# DAC_board.net
KiCad netlist of a schematic drawn in Altium Designer
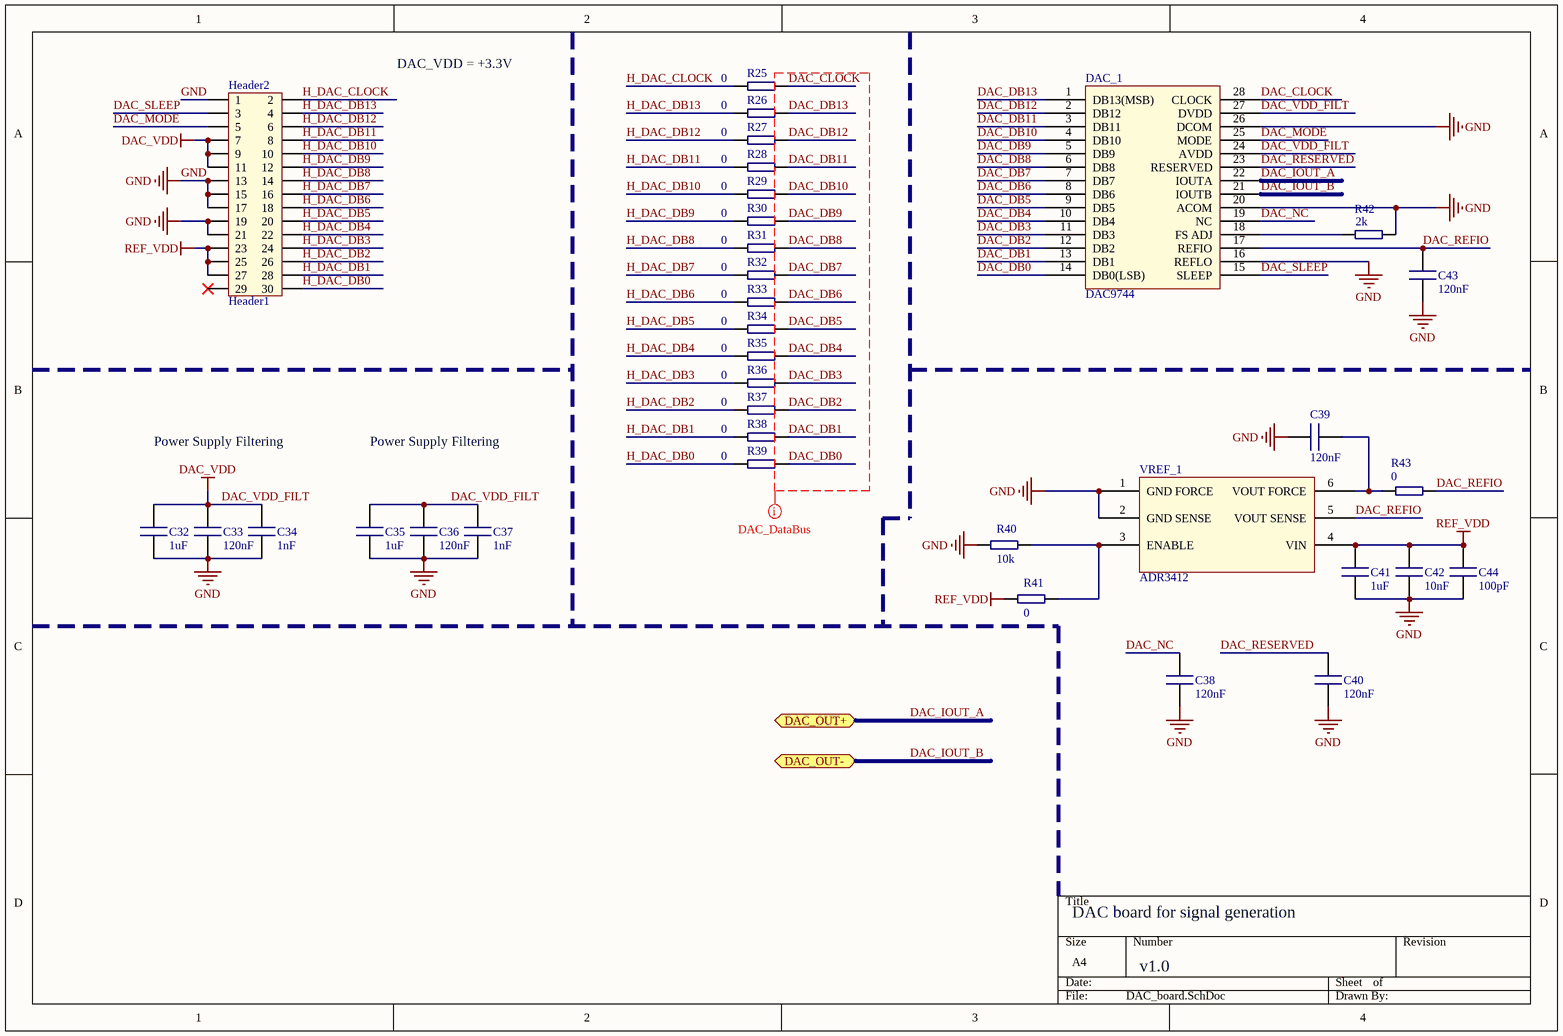
[diagram p0: DAC_board.SchDoc]

(export (version "E")
  (design (tool "Eeschema 10.0.6"))
  (components
    (comp (ref "C32")
      (value "1uF")
      (footprint "0805 SMD Passive")
      (description "SMD Capacitor")
      (fields (field (name "Comment") "Cap1"))
      (libsource (lib "RadioProjectSchLib") (part "Cap1"))
    )
    (comp (ref "C33")
      (value "120nF")
      (footprint "0805 SMD Passive")
      (description "SMD Capacitor")
      (fields (field (name "Comment") "Cap1"))
      (libsource (lib "RadioProjectSchLib") (part "Cap1"))
    )
    (comp (ref "C34")
      (value "1nF")
      (footprint "0805 SMD Passive")
      (description "SMD Capacitor")
      (fields (field (name "Comment") "Cap1"))
      (libsource (lib "RadioProjectSchLib") (part "Cap1"))
    )
    (comp (ref "C35")
      (value "1uF")
      (footprint "0805 SMD Passive")
      (description "SMD Capacitor")
      (fields (field (name "Comment") "Cap1"))
      (libsource (lib "RadioProjectSchLib") (part "Cap1"))
    )
    (comp (ref "C36")
      (value "120nF")
      (footprint "0805 SMD Passive")
      (description "SMD Capacitor")
      (fields (field (name "Comment") "Cap1"))
      (libsource (lib "RadioProjectSchLib") (part "Cap1"))
    )
    (comp (ref "C37")
      (value "1nF")
      (footprint "0805 SMD Passive")
      (description "SMD Capacitor")
      (fields (field (name "Comment") "Cap1"))
      (libsource (lib "RadioProjectSchLib") (part "Cap1"))
    )
    (comp (ref "C38")
      (value "120nF")
      (footprint "0805 SMD Passive")
      (description "SMD Capacitor")
      (fields (field (name "Comment") "Cap1"))
      (libsource (lib "RadioProjectSchLib") (part "Cap1"))
    )
    (comp (ref "C39")
      (value "120nF")
      (footprint "0805 SMD Passive")
      (description "SMD Capacitor")
      (fields (field (name "Comment") "Cap1"))
      (libsource (lib "RadioProjectSchLib") (part "Cap1"))
    )
    (comp (ref "C40")
      (value "120nF")
      (footprint "0805 SMD Passive")
      (description "SMD Capacitor")
      (fields (field (name "Comment") "Cap1"))
      (libsource (lib "RadioProjectSchLib") (part "Cap1"))
    )
    (comp (ref "C41")
      (value "1uF")
      (footprint "0805 SMD Passive")
      (description "SMD Capacitor")
      (fields (field (name "Comment") "Cap1"))
      (libsource (lib "RadioProjectSchLib") (part "Cap1"))
    )
    (comp (ref "C42")
      (value "10nF")
      (footprint "0805 SMD Passive")
      (description "SMD Capacitor")
      (fields (field (name "Comment") "Cap1"))
      (libsource (lib "RadioProjectSchLib") (part "Cap1"))
    )
    (comp (ref "C43")
      (value "120nF")
      (footprint "0805 SMD Passive")
      (description "SMD Capacitor")
      (fields (field (name "Comment") "Cap1"))
      (libsource (lib "RadioProjectSchLib") (part "Cap1"))
    )
    (comp (ref "C44")
      (value "100pF")
      (footprint "0805 SMD Passive")
      (description "SMD Capacitor")
      (fields (field (name "Comment") "Cap1"))
      (libsource (lib "RadioProjectSchLib") (part "Cap1"))
    )
    (comp (ref "DAC_1")
      (value "DAC9744")
      (footprint "AD9744")
      (description "Digital Analog Converter")
      (fields (field (name "MANUFACTURER") "Analog Devices") (field (name "PARTNUMBER") "AD9744"))
      (libsource (lib "RadioProjectSchLib") (part "AD9744"))
    )
    (comp (ref "Header2")
      (value "Header1")
      (footprint "Header1")
      (description "29 Pin Header")
      (fields (field (name "PARTNUMBER") "TLW-115-01-G-D-002-RA"))
      (libsource (lib "RadioProjectSchLib") (part "Header1"))
    )
    (comp (ref "R25")
      (value "0")
      (footprint "0805 SMD Passive")
      (description "SMD Resistor")
      (fields (field (name "Comment") "Resistor"))
      (libsource (lib "RadioProjectSchLib") (part "Res1"))
    )
    (comp (ref "R26")
      (value "0")
      (footprint "0805 SMD Passive")
      (description "SMD Resistor")
      (fields (field (name "Comment") "Resistor"))
      (libsource (lib "RadioProjectSchLib") (part "Res1"))
    )
    (comp (ref "R27")
      (value "0")
      (footprint "0805 SMD Passive")
      (description "SMD Resistor")
      (fields (field (name "Comment") "Resistor"))
      (libsource (lib "RadioProjectSchLib") (part "Res1"))
    )
    (comp (ref "R28")
      (value "0")
      (footprint "0805 SMD Passive")
      (description "SMD Resistor")
      (fields (field (name "Comment") "Resistor"))
      (libsource (lib "RadioProjectSchLib") (part "Res1"))
    )
    (comp (ref "R29")
      (value "0")
      (footprint "0805 SMD Passive")
      (description "SMD Resistor")
      (fields (field (name "Comment") "Resistor"))
      (libsource (lib "RadioProjectSchLib") (part "Res1"))
    )
    (comp (ref "R30")
      (value "0")
      (footprint "0805 SMD Passive")
      (description "SMD Resistor")
      (fields (field (name "Comment") "Resistor"))
      (libsource (lib "RadioProjectSchLib") (part "Res1"))
    )
    (comp (ref "R31")
      (value "0")
      (footprint "0805 SMD Passive")
      (description "SMD Resistor")
      (fields (field (name "Comment") "Resistor"))
      (libsource (lib "RadioProjectSchLib") (part "Res1"))
    )
    (comp (ref "R32")
      (value "0")
      (footprint "0805 SMD Passive")
      (description "SMD Resistor")
      (fields (field (name "Comment") "Resistor"))
      (libsource (lib "RadioProjectSchLib") (part "Res1"))
    )
    (comp (ref "R33")
      (value "0")
      (footprint "0805 SMD Passive")
      (description "SMD Resistor")
      (fields (field (name "Comment") "Resistor"))
      (libsource (lib "RadioProjectSchLib") (part "Res1"))
    )
    (comp (ref "R34")
      (value "0")
      (footprint "0805 SMD Passive")
      (description "SMD Resistor")
      (fields (field (name "Comment") "Resistor"))
      (libsource (lib "RadioProjectSchLib") (part "Res1"))
    )
    (comp (ref "R35")
      (value "0")
      (footprint "0805 SMD Passive")
      (description "SMD Resistor")
      (fields (field (name "Comment") "Resistor"))
      (libsource (lib "RadioProjectSchLib") (part "Res1"))
    )
    (comp (ref "R36")
      (value "0")
      (footprint "0805 SMD Passive")
      (description "SMD Resistor")
      (fields (field (name "Comment") "Resistor"))
      (libsource (lib "RadioProjectSchLib") (part "Res1"))
    )
    (comp (ref "R37")
      (value "0")
      (footprint "0805 SMD Passive")
      (description "SMD Resistor")
      (fields (field (name "Comment") "Resistor"))
      (libsource (lib "RadioProjectSchLib") (part "Res1"))
    )
    (comp (ref "R38")
      (value "0")
      (footprint "0805 SMD Passive")
      (description "SMD Resistor")
      (fields (field (name "Comment") "Resistor"))
      (libsource (lib "RadioProjectSchLib") (part "Res1"))
    )
    (comp (ref "R39")
      (value "0")
      (footprint "0805 SMD Passive")
      (description "SMD Resistor")
      (fields (field (name "Comment") "Resistor"))
      (libsource (lib "RadioProjectSchLib") (part "Res1"))
    )
    (comp (ref "R40")
      (value "10k")
      (footprint "0805 SMD Passive")
      (description "SMD Resistor")
      (fields (field (name "Comment") "Resistor"))
      (libsource (lib "RadioProjectSchLib") (part "Res1"))
    )
    (comp (ref "R41")
      (value "0")
      (footprint "0805 SMD Passive")
      (description "SMD Resistor")
      (fields (field (name "Comment") "Resistor"))
      (libsource (lib "RadioProjectSchLib") (part "Res1"))
    )
    (comp (ref "R42")
      (value "2k")
      (footprint "0805 SMD Passive")
      (description "SMD Resistor")
      (fields (field (name "Comment") "Resistor"))
      (libsource (lib "RadioProjectSchLib") (part "Res1"))
    )
    (comp (ref "R43")
      (value "0")
      (footprint "0805 SMD Passive")
      (description "SMD Resistor")
      (fields (field (name "Comment") "Resistor"))
      (libsource (lib "RadioProjectSchLib") (part "Res1"))
    )
    (comp (ref "VREF_1")
      (value "ADR3412")
      (footprint "ADR3412")
      (description "1.2 Voltage Ref Source")
      (fields (field (name "MANUFACTURER") "Analog Devices"))
      (libsource (lib "RadioProjectSchLib") (part "ADR3412"))
    )
  )
  (nets
    (net (code "1") (name "/DAC_CLOCK") (class "Default")
      (node (ref "DAC_1") (pin "28") (pinfunction "CLOCK_28") (pintype "passive"))
      (node (ref "R25") (pin "2") (pinfunction "*_2") (pintype "passive"))
    )
    (net (code "2") (name "/DAC_DB0") (class "Default")
      (node (ref "DAC_1") (pin "14") (pinfunction "DB0(LSB)_14") (pintype "passive"))
      (node (ref "R39") (pin "2") (pinfunction "*_2") (pintype "passive"))
    )
    (net (code "3") (name "/DAC_DB1") (class "Default")
      (node (ref "DAC_1") (pin "13") (pinfunction "DB1_13") (pintype "passive"))
      (node (ref "R38") (pin "2") (pinfunction "*_2") (pintype "passive"))
    )
    (net (code "4") (name "/DAC_DB2") (class "Default")
      (node (ref "DAC_1") (pin "12") (pinfunction "DB2_12") (pintype "passive"))
      (node (ref "R37") (pin "2") (pinfunction "*_2") (pintype "passive"))
    )
    (net (code "5") (name "/DAC_DB3") (class "Default")
      (node (ref "DAC_1") (pin "11") (pinfunction "DB3_11") (pintype "passive"))
      (node (ref "R36") (pin "2") (pinfunction "*_2") (pintype "passive"))
    )
    (net (code "6") (name "/DAC_DB4") (class "Default")
      (node (ref "DAC_1") (pin "10") (pinfunction "DB4_10") (pintype "passive"))
      (node (ref "R35") (pin "2") (pinfunction "*_2") (pintype "passive"))
    )
    (net (code "7") (name "/DAC_DB5") (class "Default")
      (node (ref "DAC_1") (pin "9") (pinfunction "DB5_9") (pintype "passive"))
      (node (ref "R34") (pin "2") (pinfunction "*_2") (pintype "passive"))
    )
    (net (code "8") (name "/DAC_DB6") (class "Default")
      (node (ref "DAC_1") (pin "8") (pinfunction "DB6_8") (pintype "passive"))
      (node (ref "R33") (pin "2") (pinfunction "*_2") (pintype "passive"))
    )
    (net (code "9") (name "/DAC_DB7") (class "Default")
      (node (ref "DAC_1") (pin "7") (pinfunction "DB7_7") (pintype "passive"))
      (node (ref "R32") (pin "2") (pinfunction "*_2") (pintype "passive"))
    )
    (net (code "10") (name "/DAC_DB8") (class "Default")
      (node (ref "DAC_1") (pin "6") (pinfunction "DB8_6") (pintype "passive"))
      (node (ref "R31") (pin "2") (pinfunction "*_2") (pintype "passive"))
    )
    (net (code "11") (name "/DAC_DB9") (class "Default")
      (node (ref "DAC_1") (pin "5") (pinfunction "DB9_5") (pintype "passive"))
      (node (ref "R30") (pin "2") (pinfunction "*_2") (pintype "passive"))
    )
    (net (code "12") (name "/DAC_DB10") (class "Default")
      (node (ref "DAC_1") (pin "4") (pinfunction "DB10_4") (pintype "passive"))
      (node (ref "R29") (pin "2") (pinfunction "*_2") (pintype "passive"))
    )
    (net (code "13") (name "/DAC_DB11") (class "Default")
      (node (ref "DAC_1") (pin "3") (pinfunction "DB11_3") (pintype "passive"))
      (node (ref "R28") (pin "2") (pinfunction "*_2") (pintype "passive"))
    )
    (net (code "14") (name "/DAC_DB12") (class "Default")
      (node (ref "DAC_1") (pin "2") (pinfunction "DB12_2") (pintype "passive"))
      (node (ref "R27") (pin "2") (pinfunction "*_2") (pintype "passive"))
    )
    (net (code "15") (name "/DAC_DB13") (class "Default")
      (node (ref "DAC_1") (pin "1") (pinfunction "DB13(MSB)_1") (pintype "passive"))
      (node (ref "R26") (pin "2") (pinfunction "*_2") (pintype "passive"))
    )
    (net (code "16") (name "/DAC_IOUT_A") (class "Default")
      (node (ref "DAC_1") (pin "22") (pinfunction "IOUTA_22") (pintype "passive"))
    )
    (net (code "17") (name "/DAC_IOUT_B") (class "Default")
      (node (ref "DAC_1") (pin "21") (pinfunction "IOUTB_21") (pintype "passive"))
    )
    (net (code "18") (name "/DAC_MODE") (class "Default")
      (node (ref "DAC_1") (pin "25") (pinfunction "MODE_25") (pintype "passive"))
      (node (ref "Header2") (pin "5") (pinfunction "5_5") (pintype "passive"))
    )
    (net (code "19") (name "/DAC_NC") (class "Default")
      (node (ref "C38") (pin "1") (pinfunction "*_1") (pintype "passive"))
      (node (ref "DAC_1") (pin "19") (pinfunction "NC_19") (pintype "passive"))
    )
    (net (code "20") (name "/DAC_REFIO") (class "Default")
      (node (ref "C43") (pin "1") (pinfunction "*_1") (pintype "passive"))
      (node (ref "DAC_1") (pin "17") (pinfunction "REFIO_17") (pintype "passive"))
      (node (ref "R43") (pin "2") (pinfunction "*_2") (pintype "passive"))
      (node (ref "VREF_1") (pin "5") (pinfunction "VOUT_SENSE_5") (pintype "passive"))
    )
    (net (code "21") (name "/DAC_RESERVED") (class "Default")
      (node (ref "C40") (pin "1") (pinfunction "*_1") (pintype "passive"))
      (node (ref "DAC_1") (pin "23") (pinfunction "RESERVED_23") (pintype "passive"))
    )
    (net (code "22") (name "/DAC_SLEEP") (class "Default")
      (node (ref "DAC_1") (pin "15") (pinfunction "SLEEP_15") (pintype "passive"))
      (node (ref "Header2") (pin "3") (pinfunction "3_3") (pintype "passive"))
    )
    (net (code "23") (name "/H_DAC_CLOCK") (class "Default")
      (node (ref "Header2") (pin "2") (pinfunction "2_2") (pintype "passive"))
      (node (ref "R25") (pin "1") (pinfunction "*_1") (pintype "passive"))
    )
    (net (code "24") (name "/H_DAC_DB0") (class "Default")
      (node (ref "Header2") (pin "30") (pinfunction "30_30") (pintype "passive"))
      (node (ref "R39") (pin "1") (pinfunction "*_1") (pintype "passive"))
    )
    (net (code "25") (name "/H_DAC_DB1") (class "Default")
      (node (ref "Header2") (pin "28") (pinfunction "28_28") (pintype "passive"))
      (node (ref "R38") (pin "1") (pinfunction "*_1") (pintype "passive"))
    )
    (net (code "26") (name "/H_DAC_DB2") (class "Default")
      (node (ref "Header2") (pin "26") (pinfunction "26_26") (pintype "passive"))
      (node (ref "R37") (pin "1") (pinfunction "*_1") (pintype "passive"))
    )
    (net (code "27") (name "/H_DAC_DB3") (class "Default")
      (node (ref "Header2") (pin "24") (pinfunction "24_24") (pintype "passive"))
      (node (ref "R36") (pin "1") (pinfunction "*_1") (pintype "passive"))
    )
    (net (code "28") (name "/H_DAC_DB4") (class "Default")
      (node (ref "Header2") (pin "22") (pinfunction "22_22") (pintype "passive"))
      (node (ref "R35") (pin "1") (pinfunction "*_1") (pintype "passive"))
    )
    (net (code "29") (name "/H_DAC_DB5") (class "Default")
      (node (ref "Header2") (pin "20") (pinfunction "20_20") (pintype "passive"))
      (node (ref "R34") (pin "1") (pinfunction "*_1") (pintype "passive"))
    )
    (net (code "30") (name "/H_DAC_DB6") (class "Default")
      (node (ref "Header2") (pin "18") (pinfunction "18_18") (pintype "passive"))
      (node (ref "R33") (pin "1") (pinfunction "*_1") (pintype "passive"))
    )
    (net (code "31") (name "/H_DAC_DB7") (class "Default")
      (node (ref "Header2") (pin "16") (pinfunction "16_16") (pintype "passive"))
      (node (ref "R32") (pin "1") (pinfunction "*_1") (pintype "passive"))
    )
    (net (code "32") (name "/H_DAC_DB8") (class "Default")
      (node (ref "Header2") (pin "14") (pinfunction "14_14") (pintype "passive"))
      (node (ref "R31") (pin "1") (pinfunction "*_1") (pintype "passive"))
    )
    (net (code "33") (name "/H_DAC_DB9") (class "Default")
      (node (ref "Header2") (pin "12") (pinfunction "12_12") (pintype "passive"))
      (node (ref "R30") (pin "1") (pinfunction "*_1") (pintype "passive"))
    )
    (net (code "34") (name "/H_DAC_DB10") (class "Default")
      (node (ref "Header2") (pin "10") (pinfunction "10_10") (pintype "passive"))
      (node (ref "R29") (pin "1") (pinfunction "*_1") (pintype "passive"))
    )
    (net (code "35") (name "/H_DAC_DB11") (class "Default")
      (node (ref "Header2") (pin "8") (pinfunction "8_8") (pintype "passive"))
      (node (ref "R28") (pin "1") (pinfunction "*_1") (pintype "passive"))
    )
    (net (code "36") (name "/H_DAC_DB12") (class "Default")
      (node (ref "Header2") (pin "6") (pinfunction "6_6") (pintype "passive"))
      (node (ref "R27") (pin "1") (pinfunction "*_1") (pintype "passive"))
    )
    (net (code "37") (name "/H_DAC_DB13") (class "Default")
      (node (ref "Header2") (pin "4") (pinfunction "4_4") (pintype "passive"))
      (node (ref "R26") (pin "1") (pinfunction "*_1") (pintype "passive"))
    )
    (net (code "38") (name "DAC_VDD") (class "Default")
      (node (ref "C32") (pin "1") (pinfunction "*_1") (pintype "passive"))
      (node (ref "C33") (pin "1") (pinfunction "*_1") (pintype "passive"))
      (node (ref "C34") (pin "1") (pinfunction "*_1") (pintype "passive"))
      (node (ref "C35") (pin "1") (pinfunction "*_1") (pintype "passive"))
      (node (ref "C36") (pin "1") (pinfunction "*_1") (pintype "passive"))
      (node (ref "C37") (pin "1") (pinfunction "*_1") (pintype "passive"))
      (node (ref "DAC_1") (pin "24") (pinfunction "AVDD_24") (pintype "passive"))
      (node (ref "DAC_1") (pin "27") (pinfunction "DVDD_27") (pintype "passive"))
      (node (ref "Header2") (pin "11") (pinfunction "11_11") (pintype "passive"))
      (node (ref "Header2") (pin "7") (pinfunction "7_7") (pintype "passive"))
      (node (ref "Header2") (pin "9") (pinfunction "9_9") (pintype "passive"))
    )
    (net (code "39") (name "GND") (class "Default")
      (node (ref "C32") (pin "2") (pinfunction "*_2") (pintype "passive"))
      (node (ref "C33") (pin "2") (pinfunction "*_2") (pintype "passive"))
      (node (ref "C34") (pin "2") (pinfunction "*_2") (pintype "passive"))
      (node (ref "C35") (pin "2") (pinfunction "*_2") (pintype "passive"))
      (node (ref "C36") (pin "2") (pinfunction "*_2") (pintype "passive"))
      (node (ref "C37") (pin "2") (pinfunction "*_2") (pintype "passive"))
      (node (ref "C38") (pin "2") (pinfunction "*_2") (pintype "passive"))
      (node (ref "C39") (pin "2") (pinfunction "*_2") (pintype "passive"))
      (node (ref "C40") (pin "2") (pinfunction "*_2") (pintype "passive"))
      (node (ref "C41") (pin "2") (pinfunction "*_2") (pintype "passive"))
      (node (ref "C42") (pin "2") (pinfunction "*_2") (pintype "passive"))
      (node (ref "C43") (pin "2") (pinfunction "*_2") (pintype "passive"))
      (node (ref "C44") (pin "2") (pinfunction "*_2") (pintype "passive"))
      (node (ref "DAC_1") (pin "16") (pinfunction "REFLO_16") (pintype "passive"))
      (node (ref "DAC_1") (pin "20") (pinfunction "ACOM_20") (pintype "passive"))
      (node (ref "DAC_1") (pin "26") (pinfunction "DCOM_26") (pintype "passive"))
      (node (ref "Header2") (pin "1") (pinfunction "1_1") (pintype "passive"))
      (node (ref "Header2") (pin "13") (pinfunction "13_13") (pintype "passive"))
      (node (ref "Header2") (pin "15") (pinfunction "15_15") (pintype "passive"))
      (node (ref "Header2") (pin "17") (pinfunction "17_17") (pintype "passive"))
      (node (ref "Header2") (pin "19") (pinfunction "19_19") (pintype "passive"))
      (node (ref "Header2") (pin "21") (pinfunction "21_21") (pintype "passive"))
      (node (ref "R40") (pin "2") (pinfunction "*_2") (pintype "passive"))
      (node (ref "R42") (pin "2") (pinfunction "*_2") (pintype "passive"))
      (node (ref "VREF_1") (pin "1") (pinfunction "GND_FORCE_1") (pintype "passive"))
      (node (ref "VREF_1") (pin "2") (pinfunction "GND_SENSE_2") (pintype "passive"))
    )
    (net (code "40") (name "Net-(DAC_1-FS_ADJ)") (class "Default")
      (node (ref "DAC_1") (pin "18") (pinfunction "FS_ADJ_18") (pintype "passive"))
      (node (ref "R42") (pin "1") (pinfunction "*_1") (pintype "passive"))
    )
    (net (code "41") (name "Net-(VREF_1-ENABLE)") (class "Default")
      (node (ref "R40") (pin "1") (pinfunction "*_1") (pintype "passive"))
      (node (ref "R41") (pin "1") (pinfunction "*_1") (pintype "passive"))
      (node (ref "VREF_1") (pin "3") (pinfunction "ENABLE_3") (pintype "passive"))
    )
    (net (code "42") (name "Net-(VREF_1-VOUT_FORCE)") (class "Default")
      (node (ref "C39") (pin "1") (pinfunction "*_1") (pintype "passive"))
      (node (ref "R43") (pin "1") (pinfunction "*_1") (pintype "passive"))
      (node (ref "VREF_1") (pin "6") (pinfunction "VOUT_FORCE_6") (pintype "passive"))
    )
    (net (code "43") (name "REF_VDD") (class "Default")
      (node (ref "C41") (pin "1") (pinfunction "*_1") (pintype "passive"))
      (node (ref "C42") (pin "1") (pinfunction "*_1") (pintype "passive"))
      (node (ref "C44") (pin "1") (pinfunction "*_1") (pintype "passive"))
      (node (ref "Header2") (pin "23") (pinfunction "23_23") (pintype "passive"))
      (node (ref "Header2") (pin "25") (pinfunction "25_25") (pintype "passive"))
      (node (ref "Header2") (pin "27") (pinfunction "27_27") (pintype "passive"))
      (node (ref "R41") (pin "2") (pinfunction "*_2") (pintype "passive"))
      (node (ref "VREF_1") (pin "4") (pinfunction "VIN_4") (pintype "passive"))
    )
    (net (code "44") (name "unconnected-(Header2-Pad29)") (class "Default")
      (node (ref "Header2") (pin "29") (pinfunction "29_29") (pintype "passive+no_connect"))
    )
  )
)
